# LoRa_Test_Board_Sheet.net
KiCad netlist of a schematic drawn in Altium Designer
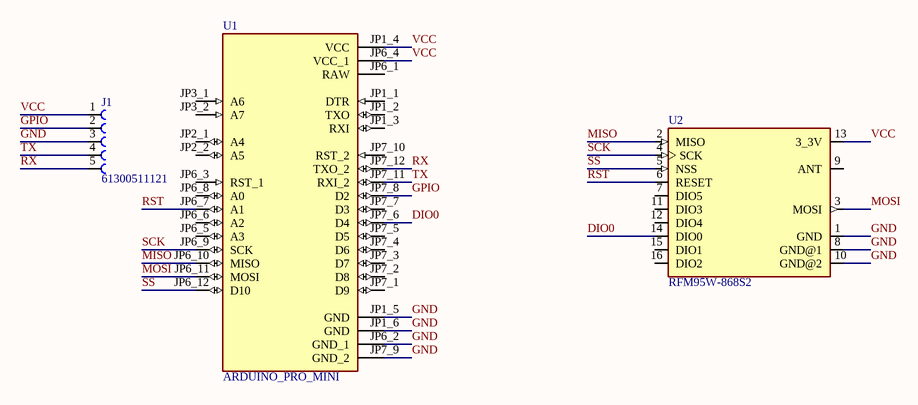
[diagram p0: LoRa_Test_Board_Sheet.SchDoc]

(export (version "E")
  (design (tool "Eeschema 10.0.6"))
  (components
    (comp (ref "J1")
      (value "61300511121")
      (footprint "61300511121")
      (description "Connector Header Through Hole 5 position 0.100 (2.54mm)")
      (fields (field (name "MF") "WÃ¼rth Elektronik"))
      (libsource (lib "5 Pin Header Male") (part "61300511121"))
    )
    (comp (ref "U1")
      (value "ARDUINO_PRO_MINI")
      (footprint "MODULE_ARDUINO_PRO_MINI")
      (fields (field (name "MP") "Arduino Pro Mini") (field (name "MF") "Arduino"))
      (libsource (lib "ARDUINO_PRO_MINI") (part "ARDUINO_PRO_MINI"))
    )
    (comp (ref "U2")
      (value "RFM95W-868S2")
      (footprint "XCVR_RFM95W-868S2")
      (description "General ISM < 1GHz LoRaâ„¢ Transceiver Module 868MHz Antenna Not Included Surface Mount")
      (fields (field (name "MF") "RF"))
      (libsource (lib "RFM95W-868S2") (part "RFM95W-868S2"))
    )
  )
  (nets
    (net (code "1") (name "/DIO0") (class "Default")
      (node (ref "U1") (pin "JP7_6") (pinfunction "D4_JP7_6") (pintype "bidirectional"))
      (node (ref "U2") (pin "14") (pinfunction "DIO0_14") (pintype "bidirectional"))
    )
    (net (code "2") (name "/GND") (class "Default")
      (node (ref "J1") (pin "3") (pinfunction "3_3") (pintype "passive"))
      (node (ref "U1") (pin "JP1_5") (pinfunction "GND_JP1_5") (pintype "power_in"))
      (node (ref "U1") (pin "JP1_6") (pinfunction "GND_JP1_6") (pintype "power_in"))
      (node (ref "U1") (pin "JP6_2") (pinfunction "GND_1_JP6_2") (pintype "power_in"))
      (node (ref "U1") (pin "JP7_9") (pinfunction "GND_2_JP7_9") (pintype "power_in"))
      (node (ref "U2") (pin "1") (pinfunction "GND_1") (pintype "power_in"))
      (node (ref "U2") (pin "10") (pinfunction "GND@2_10") (pintype "power_in"))
      (node (ref "U2") (pin "8") (pinfunction "GND@1_8") (pintype "power_in"))
    )
    (net (code "3") (name "/GPIO") (class "Default")
      (node (ref "J1") (pin "2") (pinfunction "2_2") (pintype "passive"))
      (node (ref "U1") (pin "JP7_8") (pinfunction "D2_JP7_8") (pintype "bidirectional"))
    )
    (net (code "4") (name "/MISO") (class "Default")
      (node (ref "U1") (pin "JP6_10") (pinfunction "MISO_JP6_10") (pintype "bidirectional"))
      (node (ref "U2") (pin "2") (pinfunction "MISO_2") (pintype "input"))
    )
    (net (code "5") (name "/MOSI") (class "Default")
      (node (ref "U1") (pin "JP6_11") (pinfunction "MOSI_JP6_11") (pintype "bidirectional"))
      (node (ref "U2") (pin "3") (pinfunction "MOSI_3") (pintype "output"))
    )
    (net (code "6") (name "/RST") (class "Default")
      (node (ref "U1") (pin "JP6_7") (pinfunction "A1_JP6_7") (pintype "bidirectional"))
      (node (ref "U2") (pin "6") (pinfunction "RESET_6") (pintype "bidirectional"))
    )
    (net (code "7") (name "/RX") (class "Default")
      (node (ref "J1") (pin "5") (pinfunction "5_5") (pintype "passive"))
      (node (ref "U1") (pin "JP7_12") (pinfunction "TXO_2_JP7_12") (pintype "bidirectional"))
    )
    (net (code "8") (name "/SCK") (class "Default")
      (node (ref "U1") (pin "JP6_9") (pinfunction "SCK_JP6_9") (pintype "bidirectional"))
      (node (ref "U2") (pin "4") (pinfunction "SCK_4") (pintype "input"))
    )
    (net (code "9") (name "/SS") (class "Default")
      (node (ref "U1") (pin "JP6_12") (pinfunction "D10_JP6_12") (pintype "bidirectional"))
      (node (ref "U2") (pin "5") (pinfunction "NSS_5") (pintype "input"))
    )
    (net (code "10") (name "/TX") (class "Default")
      (node (ref "J1") (pin "4") (pinfunction "4_4") (pintype "passive"))
      (node (ref "U1") (pin "JP7_11") (pinfunction "RXI_2_JP7_11") (pintype "bidirectional"))
    )
    (net (code "11") (name "/VCC") (class "Default")
      (node (ref "J1") (pin "1") (pinfunction "1_1") (pintype "passive"))
      (node (ref "U1") (pin "JP1_4") (pinfunction "VCC_JP1_4") (pintype "power_in"))
      (node (ref "U1") (pin "JP6_4") (pinfunction "VCC_1_JP6_4") (pintype "power_in"))
      (node (ref "U2") (pin "13") (pinfunction "3_3V_13") (pintype "power_in"))
    )
    (net (code "12") (name "unconnected-(U1-A0-PadJP6_8)") (class "Default")
      (node (ref "U1") (pin "JP6_8") (pinfunction "A0_JP6_8") (pintype "bidirectional"))
    )
    (net (code "13") (name "unconnected-(U1-A2-PadJP6_6)") (class "Default")
      (node (ref "U1") (pin "JP6_6") (pinfunction "A2_JP6_6") (pintype "bidirectional"))
    )
    (net (code "14") (name "unconnected-(U1-A3-PadJP6_5)") (class "Default")
      (node (ref "U1") (pin "JP6_5") (pinfunction "A3_JP6_5") (pintype "bidirectional"))
    )
    (net (code "15") (name "unconnected-(U1-A4-PadJP2_1)") (class "Default")
      (node (ref "U1") (pin "JP2_1") (pinfunction "A4_JP2_1") (pintype "bidirectional"))
    )
    (net (code "16") (name "unconnected-(U1-A5-PadJP2_2)") (class "Default")
      (node (ref "U1") (pin "JP2_2") (pinfunction "A5_JP2_2") (pintype "bidirectional"))
    )
    (net (code "17") (name "unconnected-(U1-A6-PadJP3_1)") (class "Default")
      (node (ref "U1") (pin "JP3_1") (pinfunction "A6_JP3_1") (pintype "input"))
    )
    (net (code "18") (name "unconnected-(U1-A7-PadJP3_2)") (class "Default")
      (node (ref "U1") (pin "JP3_2") (pinfunction "A7_JP3_2") (pintype "input"))
    )
    (net (code "19") (name "unconnected-(U1-D3-PadJP7_7)") (class "Default")
      (node (ref "U1") (pin "JP7_7") (pinfunction "D3_JP7_7") (pintype "bidirectional"))
    )
    (net (code "20") (name "unconnected-(U1-D5-PadJP7_5)") (class "Default")
      (node (ref "U1") (pin "JP7_5") (pinfunction "D5_JP7_5") (pintype "bidirectional"))
    )
    (net (code "21") (name "unconnected-(U1-D6-PadJP7_4)") (class "Default")
      (node (ref "U1") (pin "JP7_4") (pinfunction "D6_JP7_4") (pintype "bidirectional"))
    )
    (net (code "22") (name "unconnected-(U1-D7-PadJP7_3)") (class "Default")
      (node (ref "U1") (pin "JP7_3") (pinfunction "D7_JP7_3") (pintype "bidirectional"))
    )
    (net (code "23") (name "unconnected-(U1-D8-PadJP7_2)") (class "Default")
      (node (ref "U1") (pin "JP7_2") (pinfunction "D8_JP7_2") (pintype "bidirectional"))
    )
    (net (code "24") (name "unconnected-(U1-D9-PadJP7_1)") (class "Default")
      (node (ref "U1") (pin "JP7_1") (pinfunction "D9_JP7_1") (pintype "bidirectional"))
    )
    (net (code "25") (name "unconnected-(U1-DTR-PadJP1_1)") (class "Default")
      (node (ref "U1") (pin "JP1_1") (pinfunction "DTR_JP1_1") (pintype "input"))
    )
    (net (code "26") (name "unconnected-(U1-RAW-PadJP6_1)") (class "Default")
      (node (ref "U1") (pin "JP6_1") (pinfunction "RAW_JP6_1") (pintype "power_in"))
    )
    (net (code "27") (name "unconnected-(U1-RST_1-PadJP6_3)") (class "Default")
      (node (ref "U1") (pin "JP6_3") (pinfunction "RST_1_JP6_3") (pintype "input"))
    )
    (net (code "28") (name "unconnected-(U1-RST_2-PadJP7_10)") (class "Default")
      (node (ref "U1") (pin "JP7_10") (pinfunction "RST_2_JP7_10") (pintype "input"))
    )
    (net (code "29") (name "unconnected-(U1-RXI-PadJP1_3)") (class "Default")
      (node (ref "U1") (pin "JP1_3") (pinfunction "RXI_JP1_3") (pintype "bidirectional"))
    )
    (net (code "30") (name "unconnected-(U1-TXO-PadJP1_2)") (class "Default")
      (node (ref "U1") (pin "JP1_2") (pinfunction "TXO_JP1_2") (pintype "bidirectional"))
    )
    (net (code "31") (name "unconnected-(U2-ANT-Pad9)") (class "Default")
      (node (ref "U2") (pin "9") (pinfunction "ANT_9") (pintype "passive"))
    )
    (net (code "32") (name "unconnected-(U2-DIO1-Pad15)") (class "Default")
      (node (ref "U2") (pin "15") (pinfunction "DIO1_15") (pintype "bidirectional"))
    )
    (net (code "33") (name "unconnected-(U2-DIO2-Pad16)") (class "Default")
      (node (ref "U2") (pin "16") (pinfunction "DIO2_16") (pintype "bidirectional"))
    )
    (net (code "34") (name "unconnected-(U2-DIO3-Pad11)") (class "Default")
      (node (ref "U2") (pin "11") (pinfunction "DIO3_11") (pintype "bidirectional"))
    )
    (net (code "35") (name "unconnected-(U2-DIO4-Pad12)") (class "Default")
      (node (ref "U2") (pin "12") (pinfunction "DIO4_12") (pintype "bidirectional"))
    )
    (net (code "36") (name "unconnected-(U2-DIO5-Pad7)") (class "Default")
      (node (ref "U2") (pin "7") (pinfunction "DIO5_7") (pintype "bidirectional"))
    )
  )
)
